# wifilamp.net
KiCad netlist of a schematic drawn in EAGLE
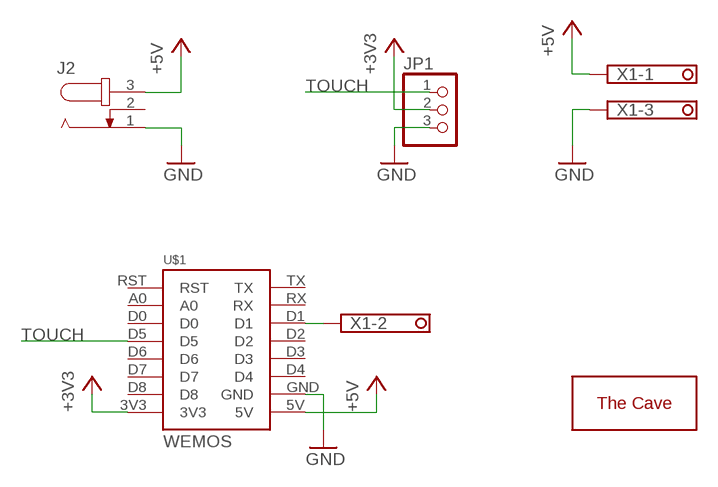
[diagram p0: schematic, sheet 1]

(export (version "E")
  (design (tool "Eeschema 10.0.6"))
  (components
    (comp (ref "J2")
      (value "PC-GK210")
      (footprint "eagle-import:PC-GK21")
      (libsource (lib "eagle-import") (part "PC-GK210"))
    )
    (comp (ref "JP1")
      (value "PINHD-1X3")
      (footprint "eagle-import:1X03")
      (libsource (lib "eagle-import") (part "PINHD-1X3"))
    )
    (comp (ref "U$1")
      (value "WEMOS")
      (footprint "eagle-import:WEMOS")
      (libsource (lib "eagle-import") (part "WEMOS"))
    )
    (comp (ref "U$2")
      (value "THECAVE_LOGO_COPPER_SMALL")
      (footprint "eagle-import:COPPER_SMALL")
      (libsource (lib "eagle-import") (part "THECAVE_LOGO_COPPER_SMALL"))
    )
    (comp (ref "X1")
      (value "1751251")
      (footprint "eagle-import:1751251")
      (libsource (lib "eagle-import") (part "1751251"))
    )
  )
  (nets
    (net (code "1") (name "+3V3") (class "Default")
      (node (ref "JP1") (pin "2") (pinfunction "2_2") (pintype "passive"))
      (node (ref "U$1") (pin "3V3") (pinfunction "3V3_3V3") (pintype "bidirectional"))
    )
    (net (code "2") (name "+5V") (class "Default")
      (node (ref "J2") (pin "3") (pinfunction "3_3") (pintype "passive"))
      (node (ref "U$1") (pin "5V") (pinfunction "5V_5V") (pintype "bidirectional"))
      (node (ref "X1") (pin "1") (pinfunction "K_1") (pintype "passive"))
    )
    (net (code "3") (name "/TOUCH") (class "Default")
      (node (ref "JP1") (pin "1") (pinfunction "1_1") (pintype "passive"))
      (node (ref "U$1") (pin "D5") (pinfunction "D5_D5") (pintype "bidirectional"))
    )
    (net (code "4") (name "GND") (class "Default")
      (node (ref "J2") (pin "1") (pinfunction "1_1") (pintype "passive"))
      (node (ref "JP1") (pin "3") (pinfunction "3_3") (pintype "passive"))
      (node (ref "U$1") (pin "GND") (pinfunction "GND_GND") (pintype "bidirectional"))
      (node (ref "X1") (pin "3") (pinfunction "K_3") (pintype "passive"))
    )
    (net (code "5") (name "Net-(X1B-K)") (class "Default")
      (node (ref "U$1") (pin "D1") (pinfunction "D1_D1") (pintype "bidirectional"))
      (node (ref "X1") (pin "2") (pinfunction "K_2") (pintype "passive"))
    )
    (net (code "6") (name "unconnected-(J2-Pad2)") (class "Default")
      (node (ref "J2") (pin "2") (pinfunction "2_2") (pintype "passive"))
    )
    (net (code "7") (name "unconnected-(U$1-PadA0)") (class "Default")
      (node (ref "U$1") (pin "A0") (pinfunction "A0_A0") (pintype "bidirectional"))
    )
    (net (code "8") (name "unconnected-(U$1-PadD0)") (class "Default")
      (node (ref "U$1") (pin "D0") (pinfunction "D0_D0") (pintype "bidirectional"))
    )
    (net (code "9") (name "unconnected-(U$1-PadD2)") (class "Default")
      (node (ref "U$1") (pin "D2") (pinfunction "D2_D2") (pintype "bidirectional"))
    )
    (net (code "10") (name "unconnected-(U$1-PadD3)") (class "Default")
      (node (ref "U$1") (pin "D3") (pinfunction "D3_D3") (pintype "bidirectional"))
    )
    (net (code "11") (name "unconnected-(U$1-PadD4)") (class "Default")
      (node (ref "U$1") (pin "D4") (pinfunction "D4_D4") (pintype "bidirectional"))
    )
    (net (code "12") (name "unconnected-(U$1-PadD6)") (class "Default")
      (node (ref "U$1") (pin "D6") (pinfunction "D6_D6") (pintype "bidirectional"))
    )
    (net (code "13") (name "unconnected-(U$1-PadD7)") (class "Default")
      (node (ref "U$1") (pin "D7") (pinfunction "D7_D7") (pintype "bidirectional"))
    )
    (net (code "14") (name "unconnected-(U$1-PadD8)") (class "Default")
      (node (ref "U$1") (pin "D8") (pinfunction "D8_D8") (pintype "bidirectional"))
    )
    (net (code "15") (name "unconnected-(U$1-PadRST)") (class "Default")
      (node (ref "U$1") (pin "RST") (pinfunction "RST_RST") (pintype "bidirectional"))
    )
    (net (code "16") (name "unconnected-(U$1-PadRX)") (class "Default")
      (node (ref "U$1") (pin "RX") (pinfunction "RX_RX") (pintype "bidirectional"))
    )
    (net (code "17") (name "unconnected-(U$1-PadTX)") (class "Default")
      (node (ref "U$1") (pin "TX") (pinfunction "TX_TX") (pintype "bidirectional"))
    )
  )
)
